# rpi_ad7705.net
KiCad netlist of a schematic drawn in EAGLE
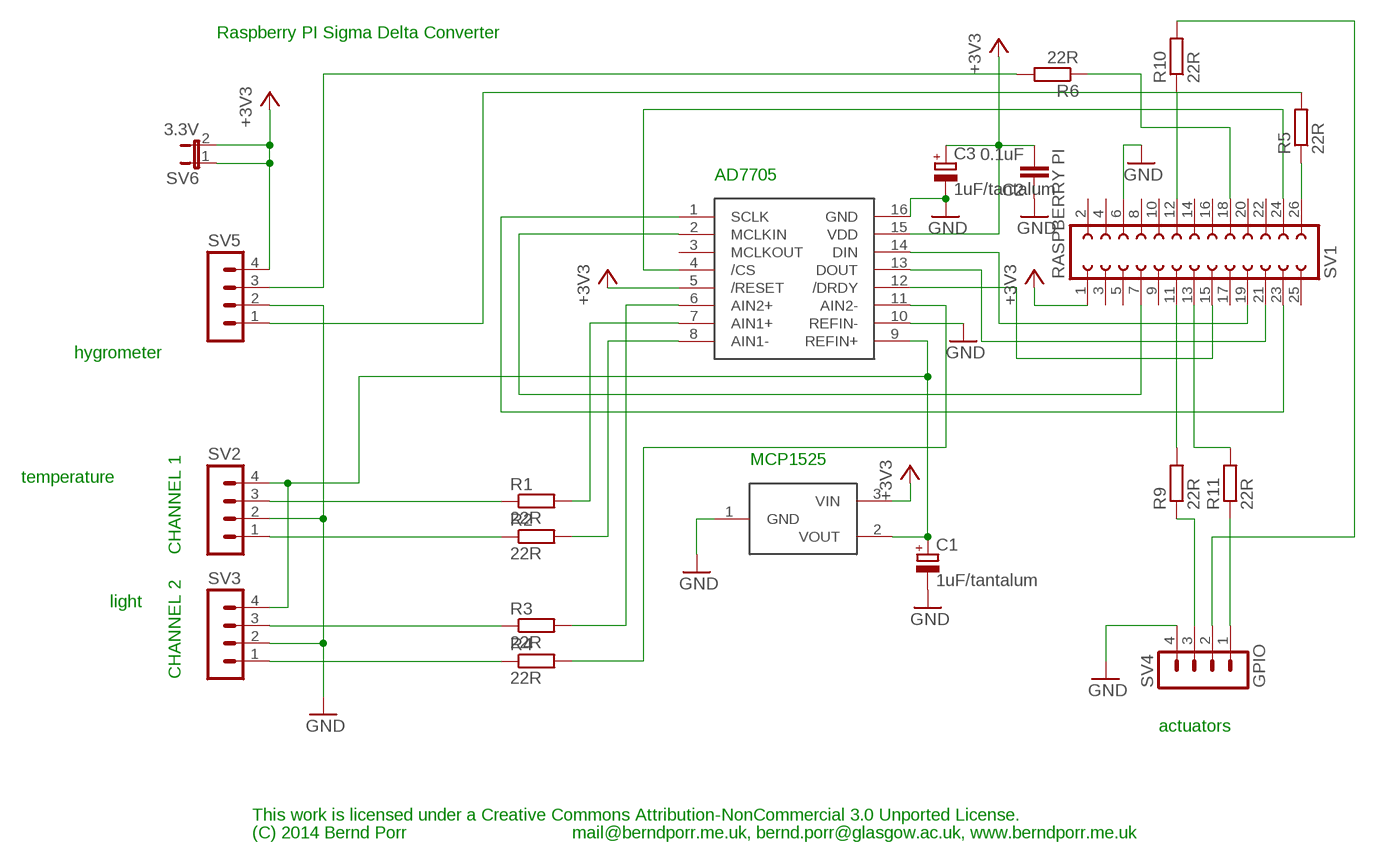
[diagram p0: schematic, sheet 1]

(export (version "E")
  (design (tool "Eeschema 10.0.6"))
  (components
    (comp (ref "C1")
      (value "1uF/tantalum")
      (footprint "eagle-import:TT2D7")
      (libsource (lib "eagle-import") (part "CPOL-EUTT2D7"))
    )
    (comp (ref "C2")
      (value "0.1uF")
      (footprint "eagle-import:C5B2.5")
      (libsource (lib "eagle-import") (part "C5/2.5"))
    )
    (comp (ref "C3")
      (value "1uF/tantalum")
      (footprint "eagle-import:TT2D7")
      (libsource (lib "eagle-import") (part "CPOL-EUTT2D7"))
    )
    (comp (ref "R1")
      (value "22R")
      (footprint "eagle-import:0207_10")
      (libsource (lib "eagle-import") (part "R-EU_0207/10"))
    )
    (comp (ref "R2")
      (value "22R")
      (footprint "eagle-import:0207_10")
      (libsource (lib "eagle-import") (part "R-EU_0207/10"))
    )
    (comp (ref "R3")
      (value "22R")
      (footprint "eagle-import:0207_10")
      (libsource (lib "eagle-import") (part "R-EU_0207/10"))
    )
    (comp (ref "R4")
      (value "22R")
      (footprint "eagle-import:0207_10")
      (libsource (lib "eagle-import") (part "R-EU_0207/10"))
    )
    (comp (ref "R5")
      (value "22R")
      (footprint "eagle-import:0207_10")
      (libsource (lib "eagle-import") (part "R-EU_0207/10"))
    )
    (comp (ref "R6")
      (value "22R")
      (footprint "eagle-import:0207_10")
      (libsource (lib "eagle-import") (part "R-EU_0207/10"))
    )
    (comp (ref "R9")
      (value "22R")
      (footprint "eagle-import:0207_10")
      (libsource (lib "eagle-import") (part "R-EU_0207/10"))
    )
    (comp (ref "R10")
      (value "22R")
      (footprint "eagle-import:0207_10")
      (libsource (lib "eagle-import") (part "R-EU_0207/10"))
    )
    (comp (ref "R11")
      (value "22R")
      (footprint "eagle-import:0207_10")
      (libsource (lib "eagle-import") (part "R-EU_0207/10"))
    )
    (comp (ref "SV1")
      (value "RASPBERRY PI")
      (footprint "eagle-import:FE13-2")
      (libsource (lib "eagle-import") (part "FE13-2"))
    )
    (comp (ref "SV2")
      (value "MA04-1")
      (footprint "eagle-import:MA04-1")
      (libsource (lib "eagle-import") (part "MA04-1"))
    )
    (comp (ref "SV3")
      (value "MA04-1")
      (footprint "eagle-import:MA04-1")
      (libsource (lib "eagle-import") (part "MA04-1"))
    )
    (comp (ref "SV4")
      (value "GPIO")
      (footprint "eagle-import:MA04-1")
      (libsource (lib "eagle-import") (part "MA04-1"))
    )
    (comp (ref "SV5")
      (value "MA04-1")
      (footprint "eagle-import:MA04-1")
      (libsource (lib "eagle-import") (part "MA04-1"))
    )
    (comp (ref "SV6")
      (value "3.3V")
      (footprint "eagle-import:JP1")
      (libsource (lib "eagle-import") (part "JP1E"))
    )
    (comp (ref "U$1")
      (value "AD7705")
      (footprint "eagle-import:DIP16")
      (libsource (lib "eagle-import") (part "AD7705"))
    )
    (comp (ref "U$2")
      (value "MCP1525")
      (footprint "eagle-import:TO92")
      (libsource (lib "eagle-import") (part "MCP1525"))
    )
  )
  (nets
    (net (code "1") (name "+3V3") (class "Default")
      (node (ref "C2") (pin "2") (pinfunction "2_2") (pintype "passive"))
      (node (ref "C3") (pin "+") (pinfunction "+_+") (pintype "passive"))
      (node (ref "SV1") (pin "1") (pinfunction "1_1") (pintype "passive"))
      (node (ref "SV5") (pin "4") (pinfunction "4_4") (pintype "passive"))
      (node (ref "SV6") (pin "1") (pinfunction "1_1") (pintype "passive"))
      (node (ref "SV6") (pin "2") (pinfunction "2_2") (pintype "passive"))
      (node (ref "U$1") (pin "15") (pinfunction "VDD_15") (pintype "power_in"))
      (node (ref "U$1") (pin "5") (pinfunction "/RESET_5") (pintype "bidirectional"))
      (node (ref "U$2") (pin "3") (pinfunction "VIN_3") (pintype "power_in"))
    )
    (net (code "2") (name "GND") (class "Default")
      (node (ref "C1") (pin "-") (pinfunction "-_-") (pintype "passive"))
      (node (ref "C2") (pin "1") (pinfunction "1_1") (pintype "passive"))
      (node (ref "C3") (pin "-") (pinfunction "-_-") (pintype "passive"))
      (node (ref "SV1") (pin "6") (pinfunction "6_6") (pintype "passive"))
      (node (ref "SV2") (pin "2") (pinfunction "2_2") (pintype "passive"))
      (node (ref "SV3") (pin "2") (pinfunction "2_2") (pintype "passive"))
      (node (ref "SV4") (pin "4") (pinfunction "4_4") (pintype "passive"))
      (node (ref "SV5") (pin "2") (pinfunction "2_2") (pintype "passive"))
      (node (ref "U$1") (pin "10") (pinfunction "REFIN-_10") (pintype "bidirectional"))
      (node (ref "U$1") (pin "16") (pinfunction "GND_16") (pintype "power_in"))
      (node (ref "U$2") (pin "1") (pinfunction "GND_1") (pintype "power_in"))
    )
    (net (code "3") (name "Net-(R1-Pad1)") (class "Default")
      (node (ref "R1") (pin "1") (pinfunction "1_1") (pintype "passive"))
      (node (ref "SV2") (pin "3") (pinfunction "3_3") (pintype "passive"))
    )
    (net (code "4") (name "Net-(R2-Pad1)") (class "Default")
      (node (ref "R2") (pin "1") (pinfunction "1_1") (pintype "passive"))
      (node (ref "SV2") (pin "1") (pinfunction "1_1") (pintype "passive"))
    )
    (net (code "5") (name "Net-(R3-Pad1)") (class "Default")
      (node (ref "R3") (pin "1") (pinfunction "1_1") (pintype "passive"))
      (node (ref "SV3") (pin "3") (pinfunction "3_3") (pintype "passive"))
    )
    (net (code "6") (name "Net-(R4-Pad1)") (class "Default")
      (node (ref "R4") (pin "1") (pinfunction "1_1") (pintype "passive"))
      (node (ref "SV3") (pin "1") (pinfunction "1_1") (pintype "passive"))
    )
    (net (code "7") (name "Net-(R5-Pad1)") (class "Default")
      (node (ref "R5") (pin "1") (pinfunction "1_1") (pintype "passive"))
      (node (ref "SV1") (pin "26") (pinfunction "26_26") (pintype "passive"))
    )
    (net (code "8") (name "Net-(R5-Pad2)") (class "Default")
      (node (ref "R5") (pin "2") (pinfunction "2_2") (pintype "passive"))
      (node (ref "SV5") (pin "1") (pinfunction "1_1") (pintype "passive"))
    )
    (net (code "9") (name "Net-(R6-Pad1)") (class "Default")
      (node (ref "R6") (pin "1") (pinfunction "1_1") (pintype "passive"))
      (node (ref "SV1") (pin "18") (pinfunction "18_18") (pintype "passive"))
    )
    (net (code "10") (name "Net-(R6-Pad2)") (class "Default")
      (node (ref "R6") (pin "2") (pinfunction "2_2") (pintype "passive"))
      (node (ref "SV5") (pin "3") (pinfunction "3_3") (pintype "passive"))
    )
    (net (code "11") (name "Net-(R9-Pad1)") (class "Default")
      (node (ref "R9") (pin "1") (pinfunction "1_1") (pintype "passive"))
      (node (ref "SV4") (pin "3") (pinfunction "3_3") (pintype "passive"))
    )
    (net (code "12") (name "Net-(R9-Pad2)") (class "Default")
      (node (ref "R9") (pin "2") (pinfunction "2_2") (pintype "passive"))
      (node (ref "SV1") (pin "11") (pinfunction "11_11") (pintype "passive"))
    )
    (net (code "13") (name "Net-(R10-Pad1)") (class "Default")
      (node (ref "R10") (pin "1") (pinfunction "1_1") (pintype "passive"))
      (node (ref "SV1") (pin "12") (pinfunction "12_12") (pintype "passive"))
    )
    (net (code "14") (name "Net-(R10-Pad2)") (class "Default")
      (node (ref "R10") (pin "2") (pinfunction "2_2") (pintype "passive"))
      (node (ref "SV4") (pin "2") (pinfunction "2_2") (pintype "passive"))
    )
    (net (code "15") (name "Net-(R11-Pad1)") (class "Default")
      (node (ref "R11") (pin "1") (pinfunction "1_1") (pintype "passive"))
      (node (ref "SV4") (pin "1") (pinfunction "1_1") (pintype "passive"))
    )
    (net (code "16") (name "Net-(R11-Pad2)") (class "Default")
      (node (ref "R11") (pin "2") (pinfunction "2_2") (pintype "passive"))
      (node (ref "SV1") (pin "13") (pinfunction "13_13") (pintype "passive"))
    )
    (net (code "17") (name "Net-(U$1-AIN1+)") (class "Default")
      (node (ref "R1") (pin "2") (pinfunction "2_2") (pintype "passive"))
      (node (ref "U$1") (pin "7") (pinfunction "AIN1+_7") (pintype "bidirectional"))
    )
    (net (code "18") (name "Net-(U$1-AIN1-)") (class "Default")
      (node (ref "R2") (pin "2") (pinfunction "2_2") (pintype "passive"))
      (node (ref "U$1") (pin "8") (pinfunction "AIN1-_8") (pintype "bidirectional"))
    )
    (net (code "19") (name "Net-(U$1-AIN2+)") (class "Default")
      (node (ref "R3") (pin "2") (pinfunction "2_2") (pintype "passive"))
      (node (ref "U$1") (pin "6") (pinfunction "AIN2+_6") (pintype "bidirectional"))
    )
    (net (code "20") (name "Net-(U$1-AIN2-)") (class "Default")
      (node (ref "R4") (pin "2") (pinfunction "2_2") (pintype "passive"))
      (node (ref "U$1") (pin "11") (pinfunction "AIN2-_11") (pintype "bidirectional"))
    )
    (net (code "21") (name "Net-(U$1-DIN)") (class "Default")
      (node (ref "SV1") (pin "19") (pinfunction "19_19") (pintype "passive"))
      (node (ref "U$1") (pin "14") (pinfunction "DIN_14") (pintype "bidirectional"))
    )
    (net (code "22") (name "Net-(U$1-DOUT)") (class "Default")
      (node (ref "SV1") (pin "21") (pinfunction "21_21") (pintype "passive"))
      (node (ref "U$1") (pin "13") (pinfunction "DOUT_13") (pintype "bidirectional"))
    )
    (net (code "23") (name "Net-(U$1-MCLKIN)") (class "Default")
      (node (ref "SV1") (pin "7") (pinfunction "7_7") (pintype "passive"))
      (node (ref "U$1") (pin "2") (pinfunction "MCLKIN_2") (pintype "bidirectional"))
    )
    (net (code "24") (name "Net-(U$1-REFIN+)") (class "Default")
      (node (ref "C1") (pin "+") (pinfunction "+_+") (pintype "passive"))
      (node (ref "SV2") (pin "4") (pinfunction "4_4") (pintype "passive"))
      (node (ref "SV3") (pin "4") (pinfunction "4_4") (pintype "passive"))
      (node (ref "U$1") (pin "9") (pinfunction "REFIN+_9") (pintype "bidirectional"))
      (node (ref "U$2") (pin "2") (pinfunction "VOUT_2") (pintype "power_in"))
    )
    (net (code "25") (name "Net-(U$1-SCLK)") (class "Default")
      (node (ref "SV1") (pin "23") (pinfunction "23_23") (pintype "passive"))
      (node (ref "U$1") (pin "1") (pinfunction "SCLK_1") (pintype "bidirectional"))
    )
    (net (code "26") (name "Net-(U$1-{slash}CS)") (class "Default")
      (node (ref "SV1") (pin "24") (pinfunction "24_24") (pintype "passive"))
      (node (ref "U$1") (pin "4") (pinfunction "/CS_4") (pintype "bidirectional"))
    )
    (net (code "27") (name "Net-(U$1-{slash}DRDY)") (class "Default")
      (node (ref "SV1") (pin "15") (pinfunction "15_15") (pintype "passive"))
      (node (ref "U$1") (pin "12") (pinfunction "/DRDY_12") (pintype "bidirectional"))
    )
    (net (code "28") (name "unconnected-(SV1-Pad2)") (class "Default")
      (node (ref "SV1") (pin "2") (pinfunction "2_2") (pintype "passive"))
    )
    (net (code "29") (name "unconnected-(SV1-Pad3)") (class "Default")
      (node (ref "SV1") (pin "3") (pinfunction "3_3") (pintype "passive"))
    )
    (net (code "30") (name "unconnected-(SV1-Pad4)") (class "Default")
      (node (ref "SV1") (pin "4") (pinfunction "4_4") (pintype "passive"))
    )
    (net (code "31") (name "unconnected-(SV1-Pad5)") (class "Default")
      (node (ref "SV1") (pin "5") (pinfunction "5_5") (pintype "passive"))
    )
    (net (code "32") (name "unconnected-(SV1-Pad8)") (class "Default")
      (node (ref "SV1") (pin "8") (pinfunction "8_8") (pintype "passive"))
    )
    (net (code "33") (name "unconnected-(SV1-Pad9)") (class "Default")
      (node (ref "SV1") (pin "9") (pinfunction "9_9") (pintype "passive"))
    )
    (net (code "34") (name "unconnected-(SV1-Pad10)") (class "Default")
      (node (ref "SV1") (pin "10") (pinfunction "10_10") (pintype "passive"))
    )
    (net (code "35") (name "unconnected-(SV1-Pad14)") (class "Default")
      (node (ref "SV1") (pin "14") (pinfunction "14_14") (pintype "passive"))
    )
    (net (code "36") (name "unconnected-(SV1-Pad16)") (class "Default")
      (node (ref "SV1") (pin "16") (pinfunction "16_16") (pintype "passive"))
    )
    (net (code "37") (name "unconnected-(SV1-Pad17)") (class "Default")
      (node (ref "SV1") (pin "17") (pinfunction "17_17") (pintype "passive"))
    )
    (net (code "38") (name "unconnected-(SV1-Pad20)") (class "Default")
      (node (ref "SV1") (pin "20") (pinfunction "20_20") (pintype "passive"))
    )
    (net (code "39") (name "unconnected-(SV1-Pad22)") (class "Default")
      (node (ref "SV1") (pin "22") (pinfunction "22_22") (pintype "passive"))
    )
    (net (code "40") (name "unconnected-(SV1-Pad25)") (class "Default")
      (node (ref "SV1") (pin "25") (pinfunction "25_25") (pintype "passive"))
    )
    (net (code "41") (name "unconnected-(U$1-MCLKOUT-Pad3)") (class "Default")
      (node (ref "U$1") (pin "3") (pinfunction "MCLKOUT_3") (pintype "bidirectional"))
    )
  )
)
